# WheelLED_LiLED_Sch.net
KiCad netlist of a schematic drawn in Altium Designer
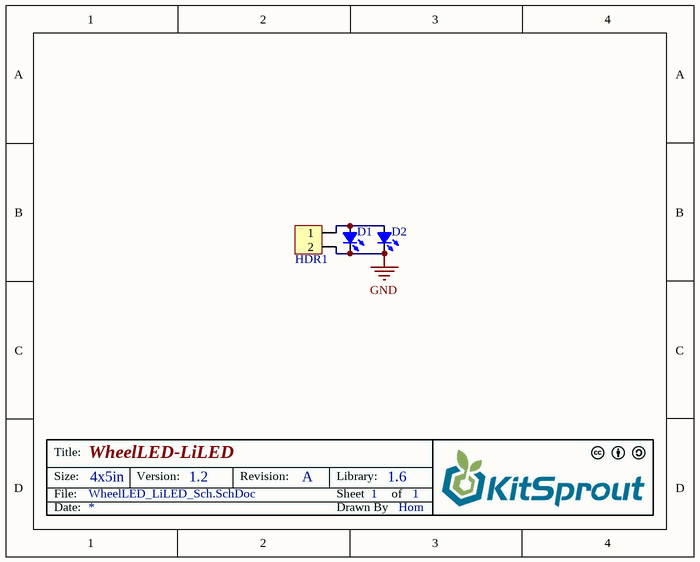
[diagram p0: WheelLED_LiLED_Sch.SchDoc]

(export (version "E")
  (design (tool "Eeschema 10.0.6"))
  (components
    (comp (ref "D1")
      (value "LED_5730")
      (footprint "PCB_ActiveLED:LED_5730_WHITE")
      (description "LED")
      (libsource (lib "SCH_Active") (part "LED_5730"))
    )
    (comp (ref "D2")
      (value "LED_5730")
      (footprint "PCB_ActiveLED:LED_5730_WHITE")
      (description "LED")
      (libsource (lib "SCH_Active") (part "LED_5730"))
    )
    (comp (ref "HDR1")
      (value "HDR1x2_2.54")
      (footprint "PCB_ConnectorHDR:HDR1X2_2.54_180F")
      (description "Header")
      (libsource (lib "SCH_ConnectorHDR") (part "HDR1x2_2.54T"))
    )
  )
  (nets
    (net (code "1") (name "GND") (class "Default")
      (node (ref "D1") (pin "2") (pinfunction "K_2") (pintype "passive"))
      (node (ref "D2") (pin "2") (pinfunction "K_2") (pintype "passive"))
      (node (ref "HDR1") (pin "2") (pinfunction "2_2") (pintype "passive"))
    )
    (net (code "2") (name "Net-(D1-A)") (class "Default")
      (node (ref "D1") (pin "1") (pinfunction "A_1") (pintype "passive"))
      (node (ref "D2") (pin "1") (pinfunction "A_1") (pintype "passive"))
      (node (ref "HDR1") (pin "1") (pinfunction "1_1") (pintype "passive"))
    )
  )
)
